# IR.net
KiCad netlist of a schematic drawn in EAGLE
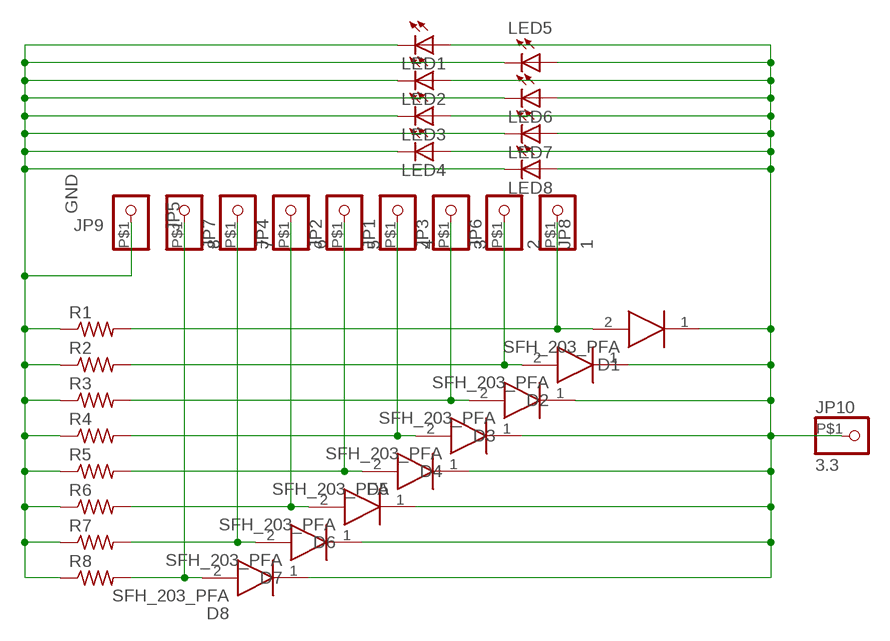
[diagram p0: schematic, sheet 1]

(export (version "E")
  (design (tool "Eeschema 10.0.6"))
  (components
    (comp (ref "D1")
      (value "SFH_203_PFA")
      (footprint "eagle-import:SFH213_1")
      (fields
        (field (name "MANUFACTURER_PART_NUMBER") "SFH 203 PFA")
        (field (name "MOUSER_PART_NUMBER") "720-SFH203PFA")
        (field (name "RS_PART_NUMBER") "6548665")
      )
      (libsource (lib "eagle-import") (part "SFH_203_PFA"))
    )
    (comp (ref "D2")
      (value "SFH_203_PFA")
      (footprint "eagle-import:SFH213_1")
      (fields
        (field (name "MANUFACTURER_PART_NUMBER") "SFH 203 PFA")
        (field (name "MOUSER_PART_NUMBER") "720-SFH203PFA")
        (field (name "RS_PART_NUMBER") "6548665")
      )
      (libsource (lib "eagle-import") (part "SFH_203_PFA"))
    )
    (comp (ref "D3")
      (value "SFH_203_PFA")
      (footprint "eagle-import:SFH213_1")
      (fields
        (field (name "MANUFACTURER_PART_NUMBER") "SFH 203 PFA")
        (field (name "MOUSER_PART_NUMBER") "720-SFH203PFA")
        (field (name "RS_PART_NUMBER") "6548665")
      )
      (libsource (lib "eagle-import") (part "SFH_203_PFA"))
    )
    (comp (ref "D4")
      (value "SFH_203_PFA")
      (footprint "eagle-import:SFH213_1")
      (fields
        (field (name "MANUFACTURER_PART_NUMBER") "SFH 203 PFA")
        (field (name "MOUSER_PART_NUMBER") "720-SFH203PFA")
        (field (name "RS_PART_NUMBER") "6548665")
      )
      (libsource (lib "eagle-import") (part "SFH_203_PFA"))
    )
    (comp (ref "D5")
      (value "SFH_203_PFA")
      (footprint "eagle-import:SFH213_1")
      (fields
        (field (name "MANUFACTURER_PART_NUMBER") "SFH 203 PFA")
        (field (name "MOUSER_PART_NUMBER") "720-SFH203PFA")
        (field (name "RS_PART_NUMBER") "6548665")
      )
      (libsource (lib "eagle-import") (part "SFH_203_PFA"))
    )
    (comp (ref "D6")
      (value "SFH_203_PFA")
      (footprint "eagle-import:SFH213_1")
      (fields
        (field (name "MANUFACTURER_PART_NUMBER") "SFH 203 PFA")
        (field (name "MOUSER_PART_NUMBER") "720-SFH203PFA")
        (field (name "RS_PART_NUMBER") "6548665")
      )
      (libsource (lib "eagle-import") (part "SFH_203_PFA"))
    )
    (comp (ref "D7")
      (value "SFH_203_PFA")
      (footprint "eagle-import:SFH213_1")
      (fields
        (field (name "MANUFACTURER_PART_NUMBER") "SFH 203 PFA")
        (field (name "MOUSER_PART_NUMBER") "720-SFH203PFA")
        (field (name "RS_PART_NUMBER") "6548665")
      )
      (libsource (lib "eagle-import") (part "SFH_203_PFA"))
    )
    (comp (ref "D8")
      (value "SFH_203_PFA")
      (footprint "eagle-import:SFH213_1")
      (fields
        (field (name "MANUFACTURER_PART_NUMBER") "SFH 203 PFA")
        (field (name "MOUSER_PART_NUMBER") "720-SFH203PFA")
        (field (name "RS_PART_NUMBER") "6548665")
      )
      (libsource (lib "eagle-import") (part "SFH_203_PFA"))
    )
    (comp (ref "JP1")
      (value "4")
      (footprint "eagle-import:1X1-BIGPOGO")
      (libsource (lib "eagle-import") (part "PINHD-1X1-BIGPOGO"))
    )
    (comp (ref "JP2")
      (value "5")
      (footprint "eagle-import:1X1-BIGPOGO")
      (libsource (lib "eagle-import") (part "PINHD-1X1-BIGPOGO"))
    )
    (comp (ref "JP3")
      (value "3")
      (footprint "eagle-import:1X1-BIGPOGO")
      (libsource (lib "eagle-import") (part "PINHD-1X1-BIGPOGO"))
    )
    (comp (ref "JP4")
      (value "6")
      (footprint "eagle-import:1X1-BIGPOGO")
      (libsource (lib "eagle-import") (part "PINHD-1X1-BIGPOGO"))
    )
    (comp (ref "JP5")
      (value "8")
      (footprint "eagle-import:1X1-BIGPOGO")
      (libsource (lib "eagle-import") (part "PINHD-1X1-BIGPOGO"))
    )
    (comp (ref "JP6")
      (value "2")
      (footprint "eagle-import:1X1-BIGPOGO")
      (libsource (lib "eagle-import") (part "PINHD-1X1-BIGPOGO"))
    )
    (comp (ref "JP7")
      (value "7")
      (footprint "eagle-import:1X1-BIGPOGO")
      (libsource (lib "eagle-import") (part "PINHD-1X1-BIGPOGO"))
    )
    (comp (ref "JP8")
      (value "1")
      (footprint "eagle-import:1X1-BIGPOGO")
      (libsource (lib "eagle-import") (part "PINHD-1X1-BIGPOGO"))
    )
    (comp (ref "JP9")
      (value "GND")
      (footprint "eagle-import:1X1-BIGPOGO")
      (libsource (lib "eagle-import") (part "PINHD-1X1-BIGPOGO"))
    )
    (comp (ref "JP10")
      (value "3.3")
      (footprint "eagle-import:1X1-BIGPOGO")
      (libsource (lib "eagle-import") (part "PINHD-1X1-BIGPOGO"))
    )
    (comp (ref "LED1")
      (value "LED5MM")
      (footprint "eagle-import:LED5MM")
      (libsource (lib "eagle-import") (part "LED5MM"))
    )
    (comp (ref "LED2")
      (value "LED5MM")
      (footprint "eagle-import:LED5MM")
      (libsource (lib "eagle-import") (part "LED5MM"))
    )
    (comp (ref "LED3")
      (value "LED5MM")
      (footprint "eagle-import:LED5MM")
      (libsource (lib "eagle-import") (part "LED5MM"))
    )
    (comp (ref "LED4")
      (value "LED5MM")
      (footprint "eagle-import:LED5MM")
      (libsource (lib "eagle-import") (part "LED5MM"))
    )
    (comp (ref "LED5")
      (value "LED5MM")
      (footprint "eagle-import:LED5MM")
      (libsource (lib "eagle-import") (part "LED5MM"))
    )
    (comp (ref "LED6")
      (value "LED5MM")
      (footprint "eagle-import:LED5MM")
      (libsource (lib "eagle-import") (part "LED5MM"))
    )
    (comp (ref "LED7")
      (value "LED5MM")
      (footprint "eagle-import:LED5MM")
      (libsource (lib "eagle-import") (part "LED5MM"))
    )
    (comp (ref "LED8")
      (value "LED5MM")
      (footprint "eagle-import:LED5MM")
      (libsource (lib "eagle-import") (part "LED5MM"))
    )
    (comp (ref "R1")
      (value "R-US_0207/10")
      (footprint "eagle-import:0207_10")
      (libsource (lib "eagle-import") (part "R-US_0207/10"))
    )
    (comp (ref "R2")
      (value "R-US_0207/10")
      (footprint "eagle-import:0207_10")
      (libsource (lib "eagle-import") (part "R-US_0207/10"))
    )
    (comp (ref "R3")
      (value "R-US_0207/10")
      (footprint "eagle-import:0207_10")
      (libsource (lib "eagle-import") (part "R-US_0207/10"))
    )
    (comp (ref "R4")
      (value "R-US_0207/10")
      (footprint "eagle-import:0207_10")
      (libsource (lib "eagle-import") (part "R-US_0207/10"))
    )
    (comp (ref "R5")
      (value "R-US_0207/10")
      (footprint "eagle-import:0207_10")
      (libsource (lib "eagle-import") (part "R-US_0207/10"))
    )
    (comp (ref "R6")
      (value "R-US_0207/10")
      (footprint "eagle-import:0207_10")
      (libsource (lib "eagle-import") (part "R-US_0207/10"))
    )
    (comp (ref "R7")
      (value "R-US_0207/10")
      (footprint "eagle-import:0207_10")
      (libsource (lib "eagle-import") (part "R-US_0207/10"))
    )
    (comp (ref "R8")
      (value "R-US_0207/10")
      (footprint "eagle-import:0207_10")
      (libsource (lib "eagle-import") (part "R-US_0207/10"))
    )
  )
  (nets
    (net (code "1") (name "Net-(D1-A)") (class "Default")
      (node (ref "D1") (pin "2") (pinfunction "A_2") (pintype "bidirectional"))
      (node (ref "JP8") (pin "P$1") (pinfunction "1_P$1") (pintype "passive"))
      (node (ref "R1") (pin "2") (pinfunction "2_2") (pintype "passive"))
    )
    (net (code "2") (name "Net-(D1-K)") (class "Default")
      (node (ref "D1") (pin "1") (pinfunction "K_1") (pintype "bidirectional"))
      (node (ref "D2") (pin "1") (pinfunction "K_1") (pintype "bidirectional"))
      (node (ref "D3") (pin "1") (pinfunction "K_1") (pintype "bidirectional"))
      (node (ref "D4") (pin "1") (pinfunction "K_1") (pintype "bidirectional"))
      (node (ref "D5") (pin "1") (pinfunction "K_1") (pintype "bidirectional"))
      (node (ref "D6") (pin "1") (pinfunction "K_1") (pintype "bidirectional"))
      (node (ref "D7") (pin "1") (pinfunction "K_1") (pintype "bidirectional"))
      (node (ref "D8") (pin "1") (pinfunction "K_1") (pintype "bidirectional"))
      (node (ref "JP10") (pin "P$1") (pinfunction "1_P$1") (pintype "passive"))
      (node (ref "LED1") (pin "A") (pinfunction "A_A") (pintype "passive"))
      (node (ref "LED2") (pin "A") (pinfunction "A_A") (pintype "passive"))
      (node (ref "LED3") (pin "A") (pinfunction "A_A") (pintype "passive"))
      (node (ref "LED4") (pin "A") (pinfunction "A_A") (pintype "passive"))
      (node (ref "LED5") (pin "A") (pinfunction "A_A") (pintype "passive"))
      (node (ref "LED6") (pin "A") (pinfunction "A_A") (pintype "passive"))
      (node (ref "LED7") (pin "A") (pinfunction "A_A") (pintype "passive"))
      (node (ref "LED8") (pin "A") (pinfunction "A_A") (pintype "passive"))
    )
    (net (code "3") (name "Net-(D2-A)") (class "Default")
      (node (ref "D2") (pin "2") (pinfunction "A_2") (pintype "bidirectional"))
      (node (ref "JP6") (pin "P$1") (pinfunction "1_P$1") (pintype "passive"))
      (node (ref "R2") (pin "2") (pinfunction "2_2") (pintype "passive"))
    )
    (net (code "4") (name "Net-(D3-A)") (class "Default")
      (node (ref "D3") (pin "2") (pinfunction "A_2") (pintype "bidirectional"))
      (node (ref "JP3") (pin "P$1") (pinfunction "1_P$1") (pintype "passive"))
      (node (ref "R3") (pin "2") (pinfunction "2_2") (pintype "passive"))
    )
    (net (code "5") (name "Net-(D4-A)") (class "Default")
      (node (ref "D4") (pin "2") (pinfunction "A_2") (pintype "bidirectional"))
      (node (ref "JP1") (pin "P$1") (pinfunction "1_P$1") (pintype "passive"))
      (node (ref "R4") (pin "2") (pinfunction "2_2") (pintype "passive"))
    )
    (net (code "6") (name "Net-(D5-A)") (class "Default")
      (node (ref "D5") (pin "2") (pinfunction "A_2") (pintype "bidirectional"))
      (node (ref "JP2") (pin "P$1") (pinfunction "1_P$1") (pintype "passive"))
      (node (ref "R5") (pin "2") (pinfunction "2_2") (pintype "passive"))
    )
    (net (code "7") (name "Net-(D6-A)") (class "Default")
      (node (ref "D6") (pin "2") (pinfunction "A_2") (pintype "bidirectional"))
      (node (ref "JP4") (pin "P$1") (pinfunction "1_P$1") (pintype "passive"))
      (node (ref "R6") (pin "2") (pinfunction "2_2") (pintype "passive"))
    )
    (net (code "8") (name "Net-(D7-A)") (class "Default")
      (node (ref "D7") (pin "2") (pinfunction "A_2") (pintype "bidirectional"))
      (node (ref "JP7") (pin "P$1") (pinfunction "1_P$1") (pintype "passive"))
      (node (ref "R7") (pin "2") (pinfunction "2_2") (pintype "passive"))
    )
    (net (code "9") (name "Net-(D8-A)") (class "Default")
      (node (ref "D8") (pin "2") (pinfunction "A_2") (pintype "bidirectional"))
      (node (ref "JP5") (pin "P$1") (pinfunction "1_P$1") (pintype "passive"))
      (node (ref "R8") (pin "2") (pinfunction "2_2") (pintype "passive"))
    )
    (net (code "10") (name "Net-(JP9-1)") (class "Default")
      (node (ref "JP9") (pin "P$1") (pinfunction "1_P$1") (pintype "passive"))
      (node (ref "LED1") (pin "K") (pinfunction "C_K") (pintype "passive"))
      (node (ref "LED2") (pin "K") (pinfunction "C_K") (pintype "passive"))
      (node (ref "LED3") (pin "K") (pinfunction "C_K") (pintype "passive"))
      (node (ref "LED4") (pin "K") (pinfunction "C_K") (pintype "passive"))
      (node (ref "LED5") (pin "K") (pinfunction "C_K") (pintype "passive"))
      (node (ref "LED6") (pin "K") (pinfunction "C_K") (pintype "passive"))
      (node (ref "LED7") (pin "K") (pinfunction "C_K") (pintype "passive"))
      (node (ref "LED8") (pin "K") (pinfunction "C_K") (pintype "passive"))
      (node (ref "R1") (pin "1") (pinfunction "1_1") (pintype "passive"))
      (node (ref "R2") (pin "1") (pinfunction "1_1") (pintype "passive"))
      (node (ref "R3") (pin "1") (pinfunction "1_1") (pintype "passive"))
      (node (ref "R4") (pin "1") (pinfunction "1_1") (pintype "passive"))
      (node (ref "R5") (pin "1") (pinfunction "1_1") (pintype "passive"))
      (node (ref "R6") (pin "1") (pinfunction "1_1") (pintype "passive"))
      (node (ref "R7") (pin "1") (pinfunction "1_1") (pintype "passive"))
      (node (ref "R8") (pin "1") (pinfunction "1_1") (pintype "passive"))
    )
  )
)
